# picopower.net
KiCad netlist of a schematic drawn in EAGLE
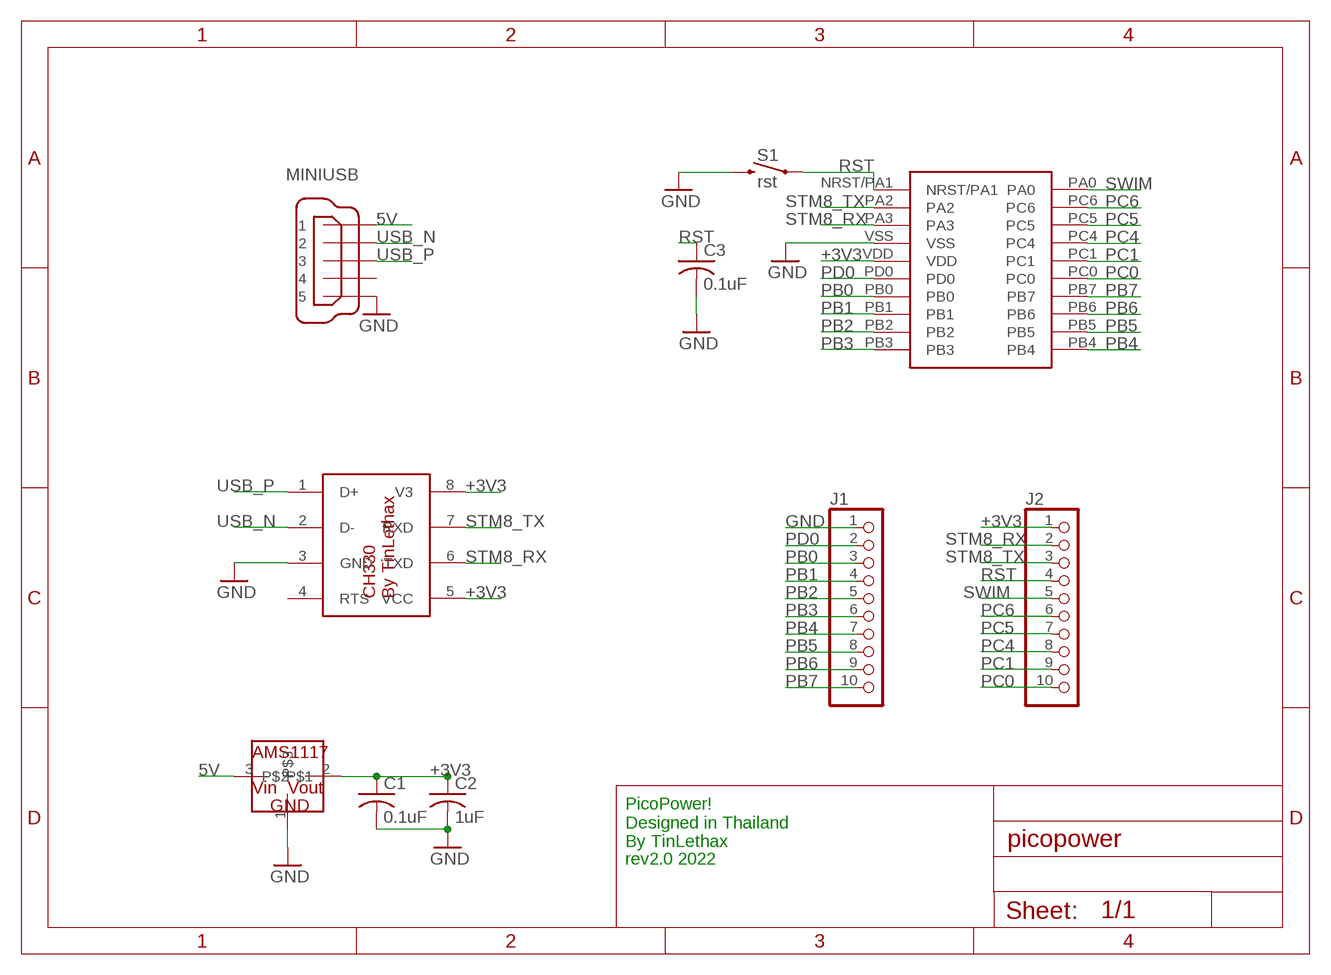
[diagram p0: schematic, sheet 1]

(export (version "E")
  (design (tool "Eeschema 10.0.6"))
  (components
    (comp (ref "C1")
      (value "0.1uF")
      (footprint "eagle-import:C0603K")
      (libsource (lib "eagle-import") (part "C-USC0603K"))
    )
    (comp (ref "C2")
      (value "1uF")
      (footprint "eagle-import:C0603K")
      (libsource (lib "eagle-import") (part "C-USC0603K"))
    )
    (comp (ref "C3")
      (value "0.1uF")
      (footprint "eagle-import:C0603K")
      (libsource (lib "eagle-import") (part "C-USC0603K"))
    )
    (comp (ref "IC1")
      (value "STM8L151F3")
      (footprint "eagle-import:UFQFPN-20")
      (libsource (lib "eagle-import") (part "STM8L151F3"))
    )
    (comp (ref "IC2")
      (value "CH330")
      (footprint "eagle-import:SOIC127P600X150-8N")
      (libsource (lib "eagle-import") (part "CH330"))
    )
    (comp (ref "IC3")
      (value "AMS1117")
      (footprint "eagle-import:SOT223")
      (libsource (lib "eagle-import") (part "AMS1117"))
    )
    (comp (ref "J1")
      (value "PINHD-1X10")
      (footprint "eagle-import:1X10-BIG")
      (libsource (lib "eagle-import") (part "PINHD-1X10"))
    )
    (comp (ref "J2")
      (value "PINHD-1X10")
      (footprint "eagle-import:1X10-BIG")
      (libsource (lib "eagle-import") (part "PINHD-1X10"))
    )
    (comp (ref "MINIUSB")
      (value "MINI-USB-UX60A-MB-5ST")
      (footprint "eagle-import:UX60A-MB-5ST")
      (libsource (lib "eagle-import") (part "MINI-USB-UX60A-MB-5ST"))
    )
    (comp (ref "S1")
      (value "rst")
      (footprint "eagle-import:TACTILE_SWITCH_SMD_RIGHT_ANGLE")
      (libsource (lib "eagle-import") (part "MOMENTARY-SWITCH-SPST-SMD-RIGHT-ANGLE"))
    )
  )
  (nets
    (net (code "1") (name "/+3V3") (class "Default")
      (node (ref "C1") (pin "1") (pinfunction "1_1") (pintype "passive"))
      (node (ref "C2") (pin "1") (pinfunction "1_1") (pintype "passive"))
      (node (ref "IC1") (pin "VDD") (pinfunction "VDD_VDD") (pintype "bidirectional"))
      (node (ref "IC2") (pin "5") (pinfunction "VCC_5") (pintype "bidirectional"))
      (node (ref "IC2") (pin "8") (pinfunction "V3_8") (pintype "bidirectional"))
      (node (ref "IC3") (pin "2") (pinfunction "P$2_2") (pintype "bidirectional"))
      (node (ref "J2") (pin "1") (pinfunction "1_1") (pintype "passive"))
    )
    (net (code "2") (name "/5V") (class "Default")
      (node (ref "IC3") (pin "3") (pinfunction "P$1_3") (pintype "bidirectional"))
      (node (ref "MINIUSB") (pin "1") (pinfunction "1_1") (pintype "input"))
    )
    (net (code "3") (name "/PB0") (class "Default")
      (node (ref "IC1") (pin "PB0") (pinfunction "PB0_PB0") (pintype "bidirectional"))
      (node (ref "J1") (pin "3") (pinfunction "3_3") (pintype "passive"))
    )
    (net (code "4") (name "/PB1") (class "Default")
      (node (ref "IC1") (pin "PB1") (pinfunction "PB1_PB1") (pintype "bidirectional"))
      (node (ref "J1") (pin "4") (pinfunction "4_4") (pintype "passive"))
    )
    (net (code "5") (name "/PB2") (class "Default")
      (node (ref "IC1") (pin "PB2") (pinfunction "PB2_PB2") (pintype "bidirectional"))
      (node (ref "J1") (pin "5") (pinfunction "5_5") (pintype "passive"))
    )
    (net (code "6") (name "/PB3") (class "Default")
      (node (ref "IC1") (pin "PB3") (pinfunction "PB3_PB3") (pintype "bidirectional"))
      (node (ref "J1") (pin "6") (pinfunction "6_6") (pintype "passive"))
    )
    (net (code "7") (name "/PB4") (class "Default")
      (node (ref "IC1") (pin "PB4") (pinfunction "PB4_PB4") (pintype "bidirectional"))
      (node (ref "J1") (pin "7") (pinfunction "7_7") (pintype "passive"))
    )
    (net (code "8") (name "/PB5") (class "Default")
      (node (ref "IC1") (pin "PB5") (pinfunction "PB5_PB5") (pintype "bidirectional"))
      (node (ref "J1") (pin "8") (pinfunction "8_8") (pintype "passive"))
    )
    (net (code "9") (name "/PB6") (class "Default")
      (node (ref "IC1") (pin "PB6") (pinfunction "PB6_PB6") (pintype "bidirectional"))
      (node (ref "J1") (pin "9") (pinfunction "9_9") (pintype "passive"))
    )
    (net (code "10") (name "/PB7") (class "Default")
      (node (ref "IC1") (pin "PB7") (pinfunction "PB7_PB7") (pintype "bidirectional"))
      (node (ref "J1") (pin "10") (pinfunction "10_10") (pintype "passive"))
    )
    (net (code "11") (name "/PC0") (class "Default")
      (node (ref "IC1") (pin "PC0") (pinfunction "PC0_PC0") (pintype "bidirectional"))
      (node (ref "J2") (pin "10") (pinfunction "10_10") (pintype "passive"))
    )
    (net (code "12") (name "/PC1") (class "Default")
      (node (ref "IC1") (pin "PC1") (pinfunction "PC1_PC1") (pintype "bidirectional"))
      (node (ref "J2") (pin "9") (pinfunction "9_9") (pintype "passive"))
    )
    (net (code "13") (name "/PC4") (class "Default")
      (node (ref "IC1") (pin "PC4") (pinfunction "PC4_PC4") (pintype "bidirectional"))
      (node (ref "J2") (pin "8") (pinfunction "8_8") (pintype "passive"))
    )
    (net (code "14") (name "/PC5") (class "Default")
      (node (ref "IC1") (pin "PC5") (pinfunction "PC5_PC5") (pintype "bidirectional"))
      (node (ref "J2") (pin "7") (pinfunction "7_7") (pintype "passive"))
    )
    (net (code "15") (name "/PC6") (class "Default")
      (node (ref "IC1") (pin "PC6") (pinfunction "PC6_PC6") (pintype "bidirectional"))
      (node (ref "J2") (pin "6") (pinfunction "6_6") (pintype "passive"))
    )
    (net (code "16") (name "/PD0") (class "Default")
      (node (ref "IC1") (pin "PD0") (pinfunction "PD0_PD0") (pintype "bidirectional"))
      (node (ref "J1") (pin "2") (pinfunction "2_2") (pintype "passive"))
    )
    (net (code "17") (name "/RST") (class "Default")
      (node (ref "C3") (pin "1") (pinfunction "1_1") (pintype "passive"))
      (node (ref "IC1") (pin "NRST/PA1") (pinfunction "NRST/PA1_NRST/PA1") (pintype "bidirectional"))
      (node (ref "J2") (pin "4") (pinfunction "4_4") (pintype "passive"))
      (node (ref "S1") (pin "1") (pinfunction "1_1") (pintype "passive"))
    )
    (net (code "18") (name "/STM8_RX") (class "Default")
      (node (ref "IC1") (pin "PA3") (pinfunction "PA3_PA3") (pintype "bidirectional"))
      (node (ref "IC2") (pin "6") (pinfunction "TXD_6") (pintype "bidirectional"))
      (node (ref "J2") (pin "2") (pinfunction "2_2") (pintype "passive"))
    )
    (net (code "19") (name "/STM8_TX") (class "Default")
      (node (ref "IC1") (pin "PA2") (pinfunction "PA2_PA2") (pintype "bidirectional"))
      (node (ref "IC2") (pin "7") (pinfunction "RXD_7") (pintype "bidirectional"))
      (node (ref "J2") (pin "3") (pinfunction "3_3") (pintype "passive"))
    )
    (net (code "20") (name "/SWIM") (class "Default")
      (node (ref "IC1") (pin "PA0") (pinfunction "PA0_PA0") (pintype "bidirectional"))
      (node (ref "J2") (pin "5") (pinfunction "5_5") (pintype "passive"))
    )
    (net (code "21") (name "/USB_N") (class "Default")
      (node (ref "IC2") (pin "2") (pinfunction "D-_2") (pintype "bidirectional"))
      (node (ref "MINIUSB") (pin "2") (pinfunction "2_2") (pintype "input"))
    )
    (net (code "22") (name "/USB_P") (class "Default")
      (node (ref "IC2") (pin "1") (pinfunction "D+_1") (pintype "bidirectional"))
      (node (ref "MINIUSB") (pin "3") (pinfunction "3_3") (pintype "input"))
    )
    (net (code "23") (name "GND") (class "Default")
      (node (ref "C1") (pin "2") (pinfunction "2_2") (pintype "passive"))
      (node (ref "C2") (pin "2") (pinfunction "2_2") (pintype "passive"))
      (node (ref "C3") (pin "2") (pinfunction "2_2") (pintype "passive"))
      (node (ref "IC1") (pin "VSS") (pinfunction "VSS_VSS") (pintype "bidirectional"))
      (node (ref "IC2") (pin "3") (pinfunction "GND_3") (pintype "bidirectional"))
      (node (ref "IC3") (pin "1") (pinfunction "P$3_1") (pintype "bidirectional"))
      (node (ref "J1") (pin "1") (pinfunction "1_1") (pintype "passive"))
      (node (ref "MINIUSB") (pin "5") (pinfunction "5_5") (pintype "input"))
      (node (ref "S1") (pin "2") (pinfunction "2_2") (pintype "passive"))
    )
    (net (code "24") (name "unconnected-(IC2-RTS-Pad4)") (class "Default")
      (node (ref "IC2") (pin "4") (pinfunction "RTS_4") (pintype "bidirectional"))
    )
    (net (code "25") (name "unconnected-(MINIUSB-Pad4)") (class "Default")
      (node (ref "MINIUSB") (pin "4") (pinfunction "4_4") (pintype "input"))
    )
  )
)
